# SH-C30A-V1_21.net
KiCad netlist of a schematic drawn in Altium Designer
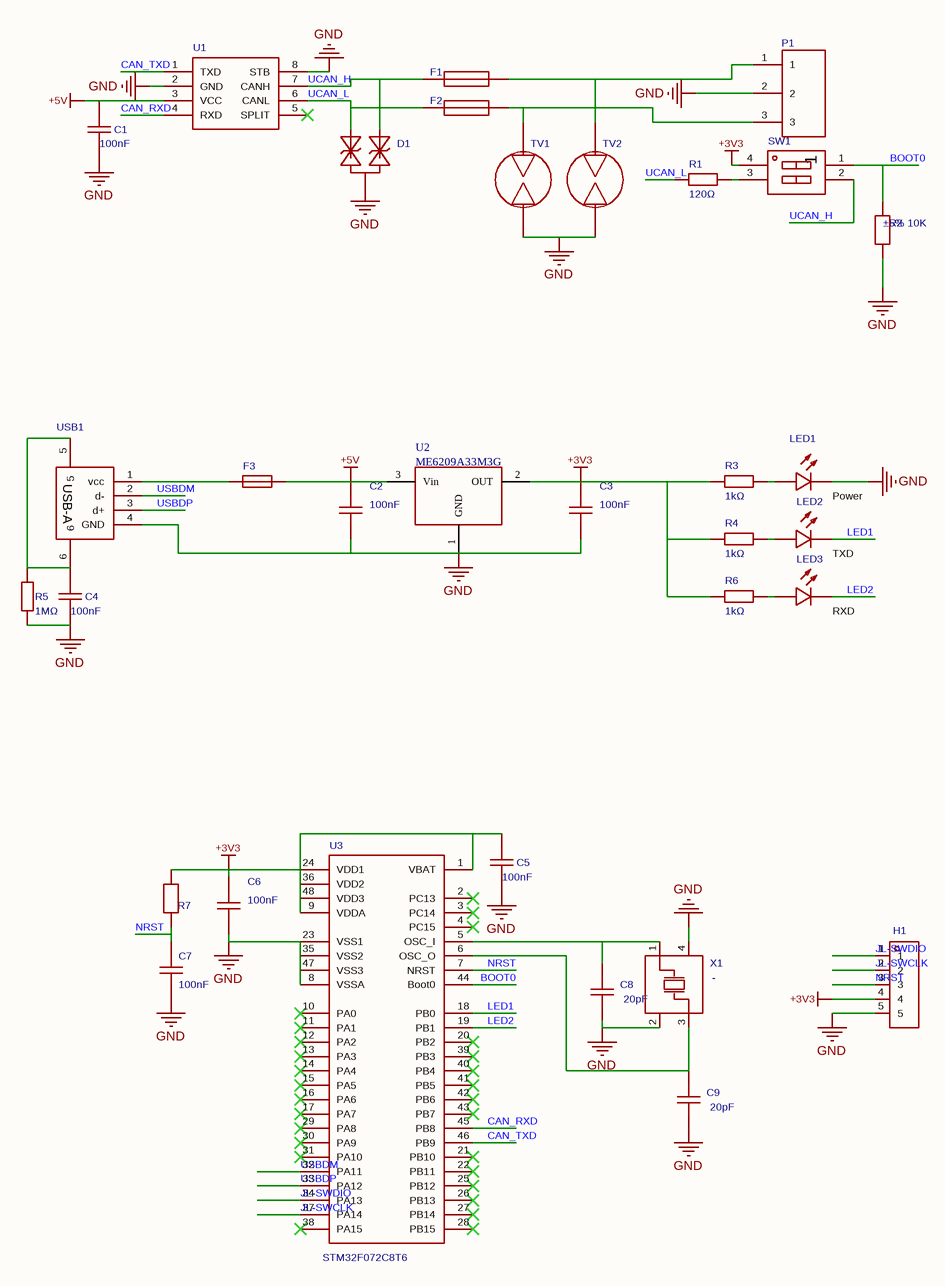
[diagram p0: SH-C30A-V1.21.SchDoc]

(export (version "E")
  (design (tool "Eeschema 10.0.6"))
  (components
    (comp (ref "C1")
      (value "100nF")
      (footprint "C0402")
      (description "Capacitance:100nF;Tolerance:±10%;Rated Voltage:50V;Temp. Coefficient:X7R;")
      (fields (field (name "MANUFACTURER") "IHHEC") (field (name "MANUFACTURERPART") "C0402X104K050T"))
      (libsource (lib "altium-import") (part "root_1_C0402X104K050T_"))
    )
    (comp (ref "C2")
      (value "100nF")
      (footprint "C0402")
      (description "Capacitance:100nF;Tolerance:±10%;Rated Voltage:50V;Temp. Coefficient:X7R;")
      (fields (field (name "MANUFACTURER") "IHHEC") (field (name "MANUFACTURERPART") "C0402X104K050T"))
      (libsource (lib "altium-import") (part "root_1_C0402X104K050T_"))
    )
    (comp (ref "C3")
      (value "100nF")
      (footprint "C0402")
      (description "Capacitance:100nF;Tolerance:±10%;Rated Voltage:50V;Temp. Coefficient:X7R;")
      (fields (field (name "MANUFACTURER") "IHHEC") (field (name "MANUFACTURERPART") "C0402X104K050T"))
      (libsource (lib "altium-import") (part "root_1_C0402X104K050T_"))
    )
    (comp (ref "C4")
      (value "100nF")
      (footprint "C0402")
      (description "Capacitance:100nF;Tolerance:±10%;Rated Voltage:50V;Temp. Coefficient:X7R;")
      (fields (field (name "MANUFACTURER") "IHHEC") (field (name "MANUFACTURERPART") "C0402X104K050T"))
      (libsource (lib "altium-import") (part "root_1_C0402X104K050T_"))
    )
    (comp (ref "C5")
      (value "100nF")
      (footprint "C0402")
      (description "Capacitance:100nF;Tolerance:±10%;Rated Voltage:50V;Temp. Coefficient:X7R;")
      (fields (field (name "MANUFACTURER") "IHHEC") (field (name "MANUFACTURERPART") "C0402X104K050T"))
      (libsource (lib "altium-import") (part "root_1_C0402X104K050T_"))
    )
    (comp (ref "C6")
      (value "100nF")
      (footprint "C0402")
      (description "Capacitance:100nF;Tolerance:±10%;Rated Voltage:50V;Temp. Coefficient:X7R;")
      (fields (field (name "MANUFACTURER") "IHHEC") (field (name "MANUFACTURERPART") "C0402X104K050T"))
      (libsource (lib "altium-import") (part "root_1_C0402X104K050T_"))
    )
    (comp (ref "C7")
      (value "100nF")
      (footprint "C0402")
      (description "Capacitance:100nF;Tolerance:±10%;Rated Voltage:50V;Temp. Coefficient:X7R;")
      (fields (field (name "MANUFACTURER") "IHHEC") (field (name "MANUFACTURERPART") "C0402X104K050T"))
      (libsource (lib "altium-import") (part "root_1_C0402X104K050T_"))
    )
    (comp (ref "C8")
      (value "20pF")
      (footprint "C0402")
      (description "Capacitance:20pF;Tolerance:±5%;Rated Voltage:50V;Temp. Coefficient:C0G;")
      (fields (field (name "MANUFACTURER") "muRata") (field (name "MANUFACTURERPART") "GRM1555C1H200JA01D"))
      (libsource (lib "altium-import") (part "root_3_GRM1555C1H200JA01D_"))
    )
    (comp (ref "C9")
      (value "20pF")
      (footprint "C0402")
      (description "Capacitance:20pF;Tolerance:±5%;Rated Voltage:50V;Temp. Coefficient:C0G;")
      (fields (field (name "MANUFACTURER") "muRata") (field (name "MANUFACTURERPART") "GRM1555C1H200JA01D"))
      (libsource (lib "altium-import") (part "root_1_GRM1555C1H200JA01D_"))
    )
    (comp (ref "D1")
      (value "~")
      (footprint "SOT-23-3_L2.9-W1.3-P1.90-LS2.4-BR")
      (fields (field (name "MANUFACTURER") "TECH PUBLIC") (field (name "MANUFACTURERPART") "TPPESD12VL2BT"))
      (libsource (lib "altium-import") (part "root_2_TPPESD12VL2BT_"))
    )
    (comp (ref "F1")
      (value "~")
      (footprint "F1206")
      (fields (field (name "MANUFACTURER") "BHFUSE") (field (name "MANUFACTURERPART") "BSMD1206-020-24V"))
      (libsource (lib "altium-import") (part "root_0_BSMD1206-020-24V_"))
    )
    (comp (ref "F2")
      (value "~")
      (footprint "F1206")
      (fields (field (name "MANUFACTURER") "BHFUSE") (field (name "MANUFACTURERPART") "BSMD1206-020-24V"))
      (libsource (lib "altium-import") (part "root_0_BSMD1206-020-24V_"))
    )
    (comp (ref "F3")
      (value "~")
      (footprint "F0805")
      (description "Max Voltage:24V;Max Current:100A;Hold Current:100mA;Trip Current:300mA;")
      (fields (field (name "MANUFACTURER") "FUZETEC") (field (name "MANUFACTURERPART") "FSMD010-24-0805-R"))
      (libsource (lib "altium-import") (part "root_0_FSMD010-24-0805-R_"))
    )
    (comp (ref "H1")
      (value "~")
      (footprint "HDR-TH_5P-P2.54-V-M")
      (fields (field (name "MANUFACTURER") "XFCN") (field (name "MANUFACTURERPART") "PZ254V-11-05P"))
      (libsource (lib "altium-import") (part "root_0_PZ254V-11-05P_"))
    )
    (comp (ref "LED1")
      (value "~")
      (footprint "LED0603-RD_RED")
      (description "Emitted Color:Red;")
      (fields (field (name "MANUFACTURER") "NationStar") (field (name "MANUFACTURERPART") "NCD0603R1"))
      (libsource (lib "altium-import") (part "root_0_mirrored_NCD0603R1_C84263_"))
    )
    (comp (ref "LED2")
      (value "~")
      (footprint "LED0603-RD")
      (description "Emitted Color:Emerald Green;")
      (fields (field (name "MANUFACTURER") "NationStar") (field (name "MANUFACTURERPART") "NCD0603G1"))
      (libsource (lib "altium-import") (part "root_0_NCD0603G1_"))
    )
    (comp (ref "LED3")
      (value "~")
      (footprint "LED0603-RD")
      (description "Emitted Color:Emerald Green;")
      (fields (field (name "MANUFACTURER") "NationStar") (field (name "MANUFACTURERPART") "NCD0603G1"))
      (libsource (lib "altium-import") (part "root_0_NCD0603G1_"))
    )
    (comp (ref "P1")
      (value "~")
      (footprint "CONN-TH_3P-P3.81_WJ124-3.81-3P")
      (fields (field (name "MANUFACTURER") "KANGNEX") (field (name "MANUFACTURERPART") "WJ124-3.81-3P"))
      (libsource (lib "altium-import") (part "root_0_mirrored_WJ124-3.81-3P_"))
    )
    (comp (ref "R1")
      (value "120Ω")
      (footprint "R0805")
      (fields
        (field (name "MANUFACTURER") "YAGEO")
        (field (name "MANUFACTURERPART") "RC0805FR-07120RL")
        (field (name "TOLERANCE") "±1%")
      )
      (libsource (lib "altium-import") (part "root_0_RC0805FR-07120RL_"))
    )
    (comp (ref "R2")
      (value "~")
      (footprint "R0402")
      (fields
        (field (name "LCSC PART NAME") "±5% 10K")
        (field (name "MANUFACTURER") "VO")
        (field (name "MANUFACTURERPART") "SCR0402J10K")
      )
      (libsource (lib "altium-import") (part "root_1_SCR0402J10K_"))
    )
    (comp (ref "R3")
      (value "1kΩ")
      (footprint "R0402")
      (fields
        (field (name "MANUFACTURER") "YAGEO")
        (field (name "MANUFACTURERPART") "RC0402JR-071KL")
        (field (name "TOLERANCE") "±5%")
      )
      (libsource (lib "altium-import") (part "root_0_RC0402JR-071KL_"))
    )
    (comp (ref "R4")
      (value "1kΩ")
      (footprint "R0402")
      (fields
        (field (name "MANUFACTURER") "YAGEO")
        (field (name "MANUFACTURERPART") "RC0402JR-071KL")
        (field (name "TOLERANCE") "±5%")
      )
      (libsource (lib "altium-import") (part "root_0_RC0402JR-071KL_"))
    )
    (comp (ref "R5")
      (value "1MΩ")
      (footprint "R0603")
      (fields
        (field (name "MANUFACTURER") "UNI-ROYAL")
        (field (name "MANUFACTURERPART") "0603WAJ0105T5E")
        (field (name "TOLERANCE") "±5%")
      )
      (libsource (lib "altium-import") (part "root_1_0603WAJ0105T5E_"))
    )
    (comp (ref "R6")
      (value "1kΩ")
      (footprint "R0402")
      (fields
        (field (name "MANUFACTURER") "YAGEO")
        (field (name "MANUFACTURERPART") "RC0402JR-071KL")
        (field (name "TOLERANCE") "±5%")
      )
      (libsource (lib "altium-import") (part "root_0_RC0402JR-071KL_"))
    )
    (comp (ref "R7")
      (value "~")
      (footprint "R0402")
      (fields (field (name "MANUFACTURER") "VO") (field (name "MANUFACTURERPART") "SCR0402J10K"))
      (libsource (lib "altium-import") (part "root_1_SCR0402J10K_"))
    )
    (comp (ref "SW1")
      (value "~")
      (footprint "SW-TH_4P-L6.5-W9.6-P2.54-LS7.62")
      (fields (field (name "MANUFACTURER") "HRO") (field (name "MANUFACTURERPART") "DP-02BP"))
      (libsource (lib "altium-import") (part "root_0_DP-02BP_"))
    )
    (comp (ref "TV1")
      (value "~")
      (footprint "DIO-DT-SMD_L4.5-W3.2")
      (fields
        (field (name "MANUFACTURER") "RUILON")
        (field (name "MANUFACTURERPART") "SMD4532-090NF")
        (field (name "TOLERANCE") "±30%")
      )
      (libsource (lib "altium-import") (part "root_0_SMD4532-090NF_"))
    )
    (comp (ref "TV2")
      (value "~")
      (footprint "DIO-DT-SMD_L4.5-W3.2")
      (fields
        (field (name "MANUFACTURER") "RUILON")
        (field (name "MANUFACTURERPART") "SMD4532-090NF")
        (field (name "TOLERANCE") "±30%")
      )
      (libsource (lib "altium-import") (part "root_0_SMD4532-090NF_"))
    )
    (comp (ref "U1")
      (value "~")
      (footprint "SOIC-8_L5.0-W4.0-P1.27-LS6.0-BL")
      (description "Type:Transceiver;Protocol:CAN Bus;")
      (fields (field (name "MANUFACTURER") "NXP") (field (name "MANUFACTURERPART") "TJA1040T/CM,118"))
      (libsource (lib "altium-import") (part "root_0_TJA1040T/CM,118_"))
    )
    (comp (ref "U2")
      (value "ME6209A33M3G")
      (footprint "SOT-23(SOT-23-3)")
      (libsource (lib "altium-import") (part "root_0_ME6209A33M3G_"))
    )
    (comp (ref "U3")
      (value "~")
      (footprint "LQFP-48_L7.0-W7.0-P0.50-LS9.0-BL")
      (description "CPU Core:ARM® Cortex®-M0;Supply Voltage:1.65V ~ 3.6V;")
      (fields (field (name "MANUFACTURER PART") "STM32F072C8T6") (field (name "MANUFACTURER") "ST"))
      (libsource (lib "altium-import") (part "root_0_STM32F072C8T6_"))
    )
    (comp (ref "USB1")
      (value "~")
      (footprint "USB-A-SMD_U-G-04WS-W-01")
      (description "Connector Type:Type-A;Standard:USB 2.0;Gender:Male;Contacts:4;Ports:1;")
      (fields (field (name "MANUFACTURER") "HRO") (field (name "MANUFACTURERPART") "U-G-04WS-W-01"))
      (libsource (lib "altium-import") (part "root_0_U-G-04WS-W-01_"))
    )
    (comp (ref "X1")
      (value "-")
      (footprint "OSC-SMD_4P-L3.2-W2.5-BL")
      (fields (field (name "MANUFACTURER") "TKD") (field (name "MANUFACTURERPART") "SX32Y024000BC1T"))
      (libsource (lib "altium-import") (part "root_3_SX32Y024000BC1T_"))
    )
  )
  (nets
    (net (code "1") (name "+3V3") (class "Default")
      (node (ref "C3") (pin "2") (pinfunction "2_2") (pintype "passive"))
      (node (ref "C5") (pin "2") (pinfunction "2_2") (pintype "passive"))
      (node (ref "C6") (pin "2") (pinfunction "2_2") (pintype "passive"))
      (node (ref "H1") (pin "4") (pinfunction "4_4") (pintype "passive"))
      (node (ref "R3") (pin "1") (pinfunction "1_1") (pintype "passive"))
      (node (ref "R4") (pin "1") (pinfunction "1_1") (pintype "passive"))
      (node (ref "R6") (pin "1") (pinfunction "1_1") (pintype "passive"))
      (node (ref "R7") (pin "2") (pinfunction "2_2") (pintype "passive"))
      (node (ref "SW1") (pin "4") (pinfunction "PIN4_4") (pintype "passive"))
      (node (ref "U2") (pin "2") (pinfunction "OUT_2") (pintype "passive"))
      (node (ref "U3") (pin "1") (pinfunction "VBAT_1") (pintype "passive"))
      (node (ref "U3") (pin "24") (pinfunction "VDD1_24") (pintype "passive"))
      (node (ref "U3") (pin "36") (pinfunction "VDD2_36") (pintype "passive"))
      (node (ref "U3") (pin "48") (pinfunction "VDD3_48") (pintype "passive"))
      (node (ref "U3") (pin "9") (pinfunction "VDDA_9") (pintype "passive"))
    )
    (net (code "2") (name "+5V") (class "Default")
      (node (ref "C1") (pin "2") (pinfunction "2_2") (pintype "passive"))
      (node (ref "C2") (pin "2") (pinfunction "2_2") (pintype "passive"))
      (node (ref "F3") (pin "2") (pinfunction "2_2") (pintype "passive"))
      (node (ref "U1") (pin "3") (pinfunction "VCC_3") (pintype "passive"))
      (node (ref "U2") (pin "3") (pinfunction "Vin_3") (pintype "passive"))
    )
    (net (code "3") (name "/BOOT0") (class "Default")
      (node (ref "R2") (pin "2") (pinfunction "2_2") (pintype "passive"))
      (node (ref "SW1") (pin "1") (pinfunction "PIN1_1") (pintype "passive"))
      (node (ref "U3") (pin "44") (pinfunction "Boot0_44") (pintype "passive"))
    )
    (net (code "4") (name "/CAN_RXD") (class "Default")
      (node (ref "U1") (pin "4") (pinfunction "RXD_4") (pintype "passive"))
      (node (ref "U3") (pin "45") (pinfunction "PB8_45") (pintype "passive"))
    )
    (net (code "5") (name "/CAN_TXD") (class "Default")
      (node (ref "U1") (pin "1") (pinfunction "TXD_1") (pintype "passive"))
      (node (ref "U3") (pin "46") (pinfunction "PB9_46") (pintype "passive"))
    )
    (net (code "6") (name "/JL-SWCLK") (class "Default")
      (node (ref "H1") (pin "2") (pinfunction "2_2") (pintype "passive"))
      (node (ref "U3") (pin "37") (pinfunction "PA14_37") (pintype "passive"))
    )
    (net (code "7") (name "/JL-SWDIO") (class "Default")
      (node (ref "H1") (pin "1") (pinfunction "1_1") (pintype "passive"))
      (node (ref "U3") (pin "34") (pinfunction "PA13_34") (pintype "passive"))
    )
    (net (code "8") (name "/LED1") (class "Default")
      (node (ref "LED2") (pin "1") (pinfunction "K_1") (pintype "passive"))
      (node (ref "U3") (pin "18") (pinfunction "PB0_18") (pintype "passive"))
    )
    (net (code "9") (name "/LED2") (class "Default")
      (node (ref "LED3") (pin "1") (pinfunction "K_1") (pintype "passive"))
      (node (ref "U3") (pin "19") (pinfunction "PB1_19") (pintype "passive"))
    )
    (net (code "10") (name "/NRST") (class "Default")
      (node (ref "C7") (pin "2") (pinfunction "2_2") (pintype "passive"))
      (node (ref "H1") (pin "3") (pinfunction "3_3") (pintype "passive"))
      (node (ref "R7") (pin "1") (pinfunction "1_1") (pintype "passive"))
      (node (ref "U3") (pin "7") (pinfunction "NRST_7") (pintype "passive"))
    )
    (net (code "11") (name "/UCAN_H") (class "Default")
      (node (ref "D1") (pin "1") (pinfunction "1_1") (pintype "passive"))
      (node (ref "F1") (pin "1") (pinfunction "1_1") (pintype "passive"))
      (node (ref "SW1") (pin "2") (pinfunction "PIN2_2") (pintype "passive"))
      (node (ref "U1") (pin "7") (pinfunction "CANH_7") (pintype "passive"))
    )
    (net (code "12") (name "/UCAN_L") (class "Default")
      (node (ref "D1") (pin "2") (pinfunction "2_2") (pintype "passive"))
      (node (ref "F2") (pin "1") (pinfunction "1_1") (pintype "passive"))
      (node (ref "R1") (pin "1") (pinfunction "1_1") (pintype "passive"))
      (node (ref "U1") (pin "6") (pinfunction "CANL_6") (pintype "passive"))
    )
    (net (code "13") (name "/USBDM") (class "Default")
      (node (ref "U3") (pin "32") (pinfunction "PA11_32") (pintype "passive"))
      (node (ref "USB1") (pin "2") (pinfunction "d-_2") (pintype "passive"))
    )
    (net (code "14") (name "/USBDP") (class "Default")
      (node (ref "U3") (pin "33") (pinfunction "PA12_33") (pintype "passive"))
      (node (ref "USB1") (pin "3") (pinfunction "d+_3") (pintype "passive"))
    )
    (net (code "15") (name "GND") (class "Default")
      (node (ref "C1") (pin "1") (pinfunction "1_1") (pintype "passive"))
      (node (ref "C2") (pin "1") (pinfunction "1_1") (pintype "passive"))
      (node (ref "C3") (pin "1") (pinfunction "1_1") (pintype "passive"))
      (node (ref "C4") (pin "1") (pinfunction "1_1") (pintype "passive"))
      (node (ref "C5") (pin "1") (pinfunction "1_1") (pintype "passive"))
      (node (ref "C6") (pin "1") (pinfunction "1_1") (pintype "passive"))
      (node (ref "C7") (pin "1") (pinfunction "1_1") (pintype "passive"))
      (node (ref "C8") (pin "2") (pinfunction "2_2") (pintype "passive"))
      (node (ref "C9") (pin "1") (pinfunction "1_1") (pintype "passive"))
      (node (ref "D1") (pin "3") (pinfunction "3_3") (pintype "passive"))
      (node (ref "H1") (pin "5") (pinfunction "5_5") (pintype "passive"))
      (node (ref "LED1") (pin "1") (pinfunction "K_1") (pintype "passive"))
      (node (ref "P1") (pin "2") (pinfunction "2_2") (pintype "passive"))
      (node (ref "R2") (pin "1") (pinfunction "1_1") (pintype "passive"))
      (node (ref "R5") (pin "1") (pinfunction "1_1") (pintype "passive"))
      (node (ref "TV1") (pin "2") (pinfunction "2_2") (pintype "passive"))
      (node (ref "TV2") (pin "2") (pinfunction "2_2") (pintype "passive"))
      (node (ref "U1") (pin "2") (pinfunction "GND_2") (pintype "passive"))
      (node (ref "U1") (pin "8") (pinfunction "STB_8") (pintype "passive"))
      (node (ref "U2") (pin "1") (pinfunction "GND_1") (pintype "passive"))
      (node (ref "U3") (pin "23") (pinfunction "VSS1_23") (pintype "passive"))
      (node (ref "U3") (pin "35") (pinfunction "VSS2_35") (pintype "passive"))
      (node (ref "U3") (pin "47") (pinfunction "VSS3_47") (pintype "passive"))
      (node (ref "U3") (pin "8") (pinfunction "VSSA_8") (pintype "passive"))
      (node (ref "USB1") (pin "4") (pinfunction "GND_4") (pintype "passive"))
      (node (ref "X1") (pin "2") (pinfunction "GND_2") (pintype "passive"))
      (node (ref "X1") (pin "4") (pinfunction "GND_4") (pintype "passive"))
    )
    (net (code "16") (name "Net-(C4-Pad2)") (class "Default")
      (node (ref "C4") (pin "2") (pinfunction "2_2") (pintype "passive"))
      (node (ref "R5") (pin "2") (pinfunction "2_2") (pintype "passive"))
      (node (ref "USB1") (pin "5") (pinfunction "5_5") (pintype "passive"))
      (node (ref "USB1") (pin "6") (pinfunction "6_6") (pintype "passive"))
    )
    (net (code "17") (name "Net-(F1-Pad2)") (class "Default")
      (node (ref "F1") (pin "2") (pinfunction "2_2") (pintype "passive"))
      (node (ref "P1") (pin "1") (pinfunction "1_1") (pintype "passive"))
      (node (ref "TV2") (pin "1") (pinfunction "1_1") (pintype "passive"))
    )
    (net (code "18") (name "Net-(F2-Pad2)") (class "Default")
      (node (ref "F2") (pin "2") (pinfunction "2_2") (pintype "passive"))
      (node (ref "P1") (pin "3") (pinfunction "3_3") (pintype "passive"))
      (node (ref "TV1") (pin "1") (pinfunction "1_1") (pintype "passive"))
    )
    (net (code "19") (name "Net-(LED1-A)") (class "Default")
      (node (ref "LED1") (pin "2") (pinfunction "A_2") (pintype "passive"))
      (node (ref "R3") (pin "2") (pinfunction "2_2") (pintype "passive"))
    )
    (net (code "20") (name "Net-(LED2-A)") (class "Default")
      (node (ref "LED2") (pin "2") (pinfunction "A_2") (pintype "passive"))
      (node (ref "R4") (pin "2") (pinfunction "2_2") (pintype "passive"))
    )
    (net (code "21") (name "Net-(LED3-A)") (class "Default")
      (node (ref "LED3") (pin "2") (pinfunction "A_2") (pintype "passive"))
      (node (ref "R6") (pin "2") (pinfunction "2_2") (pintype "passive"))
    )
    (net (code "22") (name "Net-(SW1-PIN3)") (class "Default")
      (node (ref "R1") (pin "2") (pinfunction "2_2") (pintype "passive"))
      (node (ref "SW1") (pin "3") (pinfunction "PIN3_3") (pintype "passive"))
    )
    (net (code "23") (name "Net-(U3-OSC_I)") (class "Default")
      (node (ref "C8") (pin "1") (pinfunction "1_1") (pintype "passive"))
      (node (ref "U3") (pin "5") (pinfunction "OSC_I_5") (pintype "passive"))
      (node (ref "X1") (pin "1") (pinfunction "OSC1_1") (pintype "passive"))
    )
    (net (code "24") (name "Net-(U3-OSC_O)") (class "Default")
      (node (ref "C9") (pin "2") (pinfunction "2_2") (pintype "passive"))
      (node (ref "U3") (pin "6") (pinfunction "OSC_O_6") (pintype "passive"))
      (node (ref "X1") (pin "3") (pinfunction "OSC2_3") (pintype "passive"))
    )
    (net (code "25") (name "Net-(USB1-vcc)") (class "Default")
      (node (ref "F3") (pin "1") (pinfunction "1_1") (pintype "passive"))
      (node (ref "USB1") (pin "1") (pinfunction "vcc_1") (pintype "passive"))
    )
    (net (code "26") (name "unconnected-(U1-SPLIT-Pad5)") (class "Default")
      (node (ref "U1") (pin "5") (pinfunction "SPLIT_5") (pintype "passive+no_connect"))
    )
    (net (code "27") (name "unconnected-(U3-PA0-Pad10)") (class "Default")
      (node (ref "U3") (pin "10") (pinfunction "PA0_10") (pintype "passive+no_connect"))
    )
    (net (code "28") (name "unconnected-(U3-PA1-Pad11)") (class "Default")
      (node (ref "U3") (pin "11") (pinfunction "PA1_11") (pintype "passive+no_connect"))
    )
    (net (code "29") (name "unconnected-(U3-PA2-Pad12)") (class "Default")
      (node (ref "U3") (pin "12") (pinfunction "PA2_12") (pintype "passive+no_connect"))
    )
    (net (code "30") (name "unconnected-(U3-PA3-Pad13)") (class "Default")
      (node (ref "U3") (pin "13") (pinfunction "PA3_13") (pintype "passive+no_connect"))
    )
    (net (code "31") (name "unconnected-(U3-PA4-Pad14)") (class "Default")
      (node (ref "U3") (pin "14") (pinfunction "PA4_14") (pintype "passive+no_connect"))
    )
    (net (code "32") (name "unconnected-(U3-PA5-Pad15)") (class "Default")
      (node (ref "U3") (pin "15") (pinfunction "PA5_15") (pintype "passive+no_connect"))
    )
    (net (code "33") (name "unconnected-(U3-PA6-Pad16)") (class "Default")
      (node (ref "U3") (pin "16") (pinfunction "PA6_16") (pintype "passive+no_connect"))
    )
    (net (code "34") (name "unconnected-(U3-PA7-Pad17)") (class "Default")
      (node (ref "U3") (pin "17") (pinfunction "PA7_17") (pintype "passive+no_connect"))
    )
    (net (code "35") (name "unconnected-(U3-PA8-Pad29)") (class "Default")
      (node (ref "U3") (pin "29") (pinfunction "PA8_29") (pintype "passive+no_connect"))
    )
    (net (code "36") (name "unconnected-(U3-PA9-Pad30)") (class "Default")
      (node (ref "U3") (pin "30") (pinfunction "PA9_30") (pintype "passive+no_connect"))
    )
    (net (code "37") (name "unconnected-(U3-PA10-Pad31)") (class "Default")
      (node (ref "U3") (pin "31") (pinfunction "PA10_31") (pintype "passive+no_connect"))
    )
    (net (code "38") (name "unconnected-(U3-PA15-Pad38)") (class "Default")
      (node (ref "U3") (pin "38") (pinfunction "PA15_38") (pintype "passive+no_connect"))
    )
    (net (code "39") (name "unconnected-(U3-PB2-Pad20)") (class "Default")
      (node (ref "U3") (pin "20") (pinfunction "PB2_20") (pintype "passive+no_connect"))
    )
    (net (code "40") (name "unconnected-(U3-PB3-Pad39)") (class "Default")
      (node (ref "U3") (pin "39") (pinfunction "PB3_39") (pintype "passive+no_connect"))
    )
    (net (code "41") (name "unconnected-(U3-PB4-Pad40)") (class "Default")
      (node (ref "U3") (pin "40") (pinfunction "PB4_40") (pintype "passive+no_connect"))
    )
    (net (code "42") (name "unconnected-(U3-PB5-Pad41)") (class "Default")
      (node (ref "U3") (pin "41") (pinfunction "PB5_41") (pintype "passive+no_connect"))
    )
    (net (code "43") (name "unconnected-(U3-PB6-Pad42)") (class "Default")
      (node (ref "U3") (pin "42") (pinfunction "PB6_42") (pintype "passive+no_connect"))
    )
    (net (code "44") (name "unconnected-(U3-PB7-Pad43)") (class "Default")
      (node (ref "U3") (pin "43") (pinfunction "PB7_43") (pintype "passive+no_connect"))
    )
    (net (code "45") (name "unconnected-(U3-PB10-Pad21)") (class "Default")
      (node (ref "U3") (pin "21") (pinfunction "PB10_21") (pintype "passive+no_connect"))
    )
    (net (code "46") (name "unconnected-(U3-PB11-Pad22)") (class "Default")
      (node (ref "U3") (pin "22") (pinfunction "PB11_22") (pintype "passive+no_connect"))
    )
    (net (code "47") (name "unconnected-(U3-PB12-Pad25)") (class "Default")
      (node (ref "U3") (pin "25") (pinfunction "PB12_25") (pintype "passive+no_connect"))
    )
    (net (code "48") (name "unconnected-(U3-PB13-Pad26)") (class "Default")
      (node (ref "U3") (pin "26") (pinfunction "PB13_26") (pintype "passive+no_connect"))
    )
    (net (code "49") (name "unconnected-(U3-PB14-Pad27)") (class "Default")
      (node (ref "U3") (pin "27") (pinfunction "PB14_27") (pintype "passive+no_connect"))
    )
    (net (code "50") (name "unconnected-(U3-PB15-Pad28)") (class "Default")
      (node (ref "U3") (pin "28") (pinfunction "PB15_28") (pintype "passive+no_connect"))
    )
    (net (code "51") (name "unconnected-(U3-PC13-Pad2)") (class "Default")
      (node (ref "U3") (pin "2") (pinfunction "PC13_2") (pintype "passive+no_connect"))
    )
    (net (code "52") (name "unconnected-(U3-PC14-Pad3)") (class "Default")
      (node (ref "U3") (pin "3") (pinfunction "PC14_3") (pintype "passive+no_connect"))
    )
    (net (code "53") (name "unconnected-(U3-PC15-Pad4)") (class "Default")
      (node (ref "U3") (pin "4") (pinfunction "PC15_4") (pintype "passive+no_connect"))
    )
  )
)
